# sasa5.net
KiCad netlist of a schematic drawn in EAGLE
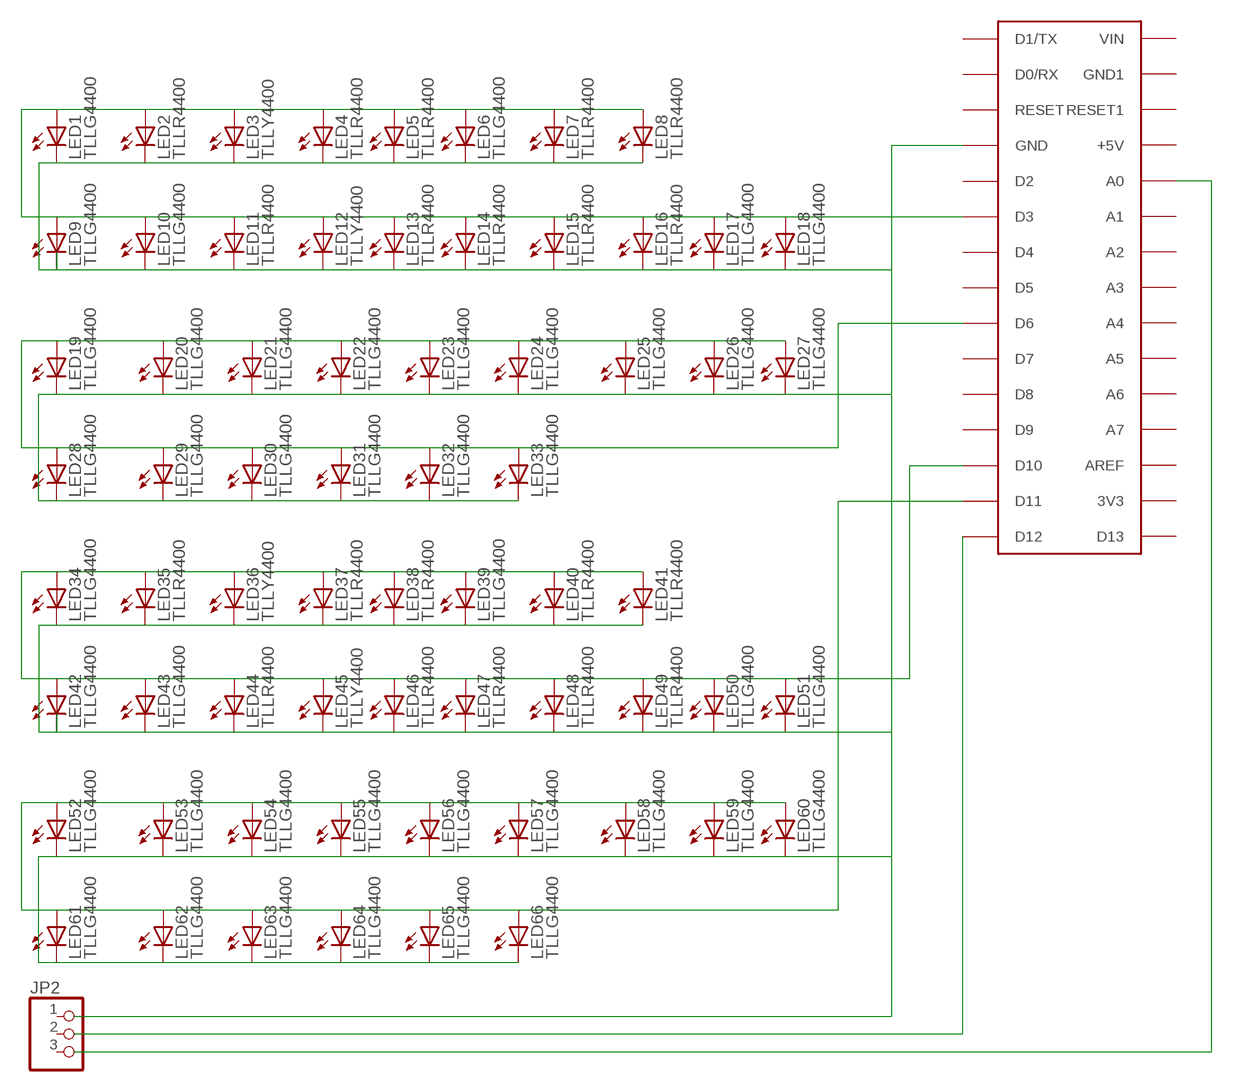
[diagram p0: schematic, sheet 1]

(export (version "E")
  (design (tool "Eeschema 10.0.6"))
  (components
    (comp (ref "JP2")
      (value "PINHD-1X3")
      (footprint "eagle-import:1X03")
      (libsource (lib "eagle-import") (part "PINHD-1X3"))
    )
    (comp (ref "LED1")
      (value "TLLG4400")
      (footprint "eagle-import:LED3MM")
      (fields (field (name "MF") "VISHAY SEMICONDUCTOR"))
      (libsource (lib "eagle-import") (part "TLLG4400"))
    )
    (comp (ref "LED2")
      (value "TLLR4400")
      (footprint "eagle-import:LED3MM")
      (fields (field (name "MF") "VISHAY SEMICONDUCTOR"))
      (libsource (lib "eagle-import") (part "TLLR4400"))
    )
    (comp (ref "LED3")
      (value "TLLY4400")
      (footprint "eagle-import:LED3MM")
      (fields (field (name "MF") "VISHAY SEMICONDUCTOR"))
      (libsource (lib "eagle-import") (part "TLLY4400"))
    )
    (comp (ref "LED4")
      (value "TLLR4400")
      (footprint "eagle-import:LED3MM")
      (fields (field (name "MF") "VISHAY SEMICONDUCTOR"))
      (libsource (lib "eagle-import") (part "TLLR4400"))
    )
    (comp (ref "LED5")
      (value "TLLR4400")
      (footprint "eagle-import:LED3MM")
      (fields (field (name "MF") "VISHAY SEMICONDUCTOR"))
      (libsource (lib "eagle-import") (part "TLLR4400"))
    )
    (comp (ref "LED6")
      (value "TLLG4400")
      (footprint "eagle-import:LED3MM")
      (fields (field (name "MF") "VISHAY SEMICONDUCTOR"))
      (libsource (lib "eagle-import") (part "TLLG4400"))
    )
    (comp (ref "LED7")
      (value "TLLR4400")
      (footprint "eagle-import:LED3MM")
      (fields (field (name "MF") "VISHAY SEMICONDUCTOR"))
      (libsource (lib "eagle-import") (part "TLLR4400"))
    )
    (comp (ref "LED8")
      (value "TLLR4400")
      (footprint "eagle-import:LED3MM")
      (fields (field (name "MF") "VISHAY SEMICONDUCTOR"))
      (libsource (lib "eagle-import") (part "TLLR4400"))
    )
    (comp (ref "LED9")
      (value "TLLG4400")
      (footprint "eagle-import:LED3MM")
      (fields (field (name "MF") "VISHAY SEMICONDUCTOR"))
      (libsource (lib "eagle-import") (part "TLLG4400"))
    )
    (comp (ref "LED10")
      (value "TLLG4400")
      (footprint "eagle-import:LED3MM")
      (fields (field (name "MF") "VISHAY SEMICONDUCTOR"))
      (libsource (lib "eagle-import") (part "TLLG4400"))
    )
    (comp (ref "LED11")
      (value "TLLR4400")
      (footprint "eagle-import:LED3MM")
      (fields (field (name "MF") "VISHAY SEMICONDUCTOR"))
      (libsource (lib "eagle-import") (part "TLLR4400"))
    )
    (comp (ref "LED12")
      (value "TLLY4400")
      (footprint "eagle-import:LED3MM")
      (fields (field (name "MF") "VISHAY SEMICONDUCTOR"))
      (libsource (lib "eagle-import") (part "TLLY4400"))
    )
    (comp (ref "LED13")
      (value "TLLR4400")
      (footprint "eagle-import:LED3MM")
      (fields (field (name "MF") "VISHAY SEMICONDUCTOR"))
      (libsource (lib "eagle-import") (part "TLLR4400"))
    )
    (comp (ref "LED14")
      (value "TLLR4400")
      (footprint "eagle-import:LED3MM")
      (fields (field (name "MF") "VISHAY SEMICONDUCTOR"))
      (libsource (lib "eagle-import") (part "TLLR4400"))
    )
    (comp (ref "LED15")
      (value "TLLR4400")
      (footprint "eagle-import:LED3MM")
      (fields (field (name "MF") "VISHAY SEMICONDUCTOR"))
      (libsource (lib "eagle-import") (part "TLLR4400"))
    )
    (comp (ref "LED16")
      (value "TLLR4400")
      (footprint "eagle-import:LED3MM")
      (fields (field (name "MF") "VISHAY SEMICONDUCTOR"))
      (libsource (lib "eagle-import") (part "TLLR4400"))
    )
    (comp (ref "LED17")
      (value "TLLG4400")
      (footprint "eagle-import:LED3MM")
      (fields (field (name "MF") "VISHAY SEMICONDUCTOR"))
      (libsource (lib "eagle-import") (part "TLLG4400"))
    )
    (comp (ref "LED18")
      (value "TLLG4400")
      (footprint "eagle-import:LED3MM")
      (fields (field (name "MF") "VISHAY SEMICONDUCTOR"))
      (libsource (lib "eagle-import") (part "TLLG4400"))
    )
    (comp (ref "LED19")
      (value "TLLG4400")
      (footprint "eagle-import:LED3MM")
      (fields (field (name "MF") "VISHAY SEMICONDUCTOR"))
      (libsource (lib "eagle-import") (part "TLLG4400"))
    )
    (comp (ref "LED20")
      (value "TLLG4400")
      (footprint "eagle-import:LED3MM")
      (fields (field (name "MF") "VISHAY SEMICONDUCTOR"))
      (libsource (lib "eagle-import") (part "TLLG4400"))
    )
    (comp (ref "LED21")
      (value "TLLG4400")
      (footprint "eagle-import:LED3MM")
      (fields (field (name "MF") "VISHAY SEMICONDUCTOR"))
      (libsource (lib "eagle-import") (part "TLLG4400"))
    )
    (comp (ref "LED22")
      (value "TLLG4400")
      (footprint "eagle-import:LED3MM")
      (fields (field (name "MF") "VISHAY SEMICONDUCTOR"))
      (libsource (lib "eagle-import") (part "TLLG4400"))
    )
    (comp (ref "LED23")
      (value "TLLG4400")
      (footprint "eagle-import:LED3MM")
      (fields (field (name "MF") "VISHAY SEMICONDUCTOR"))
      (libsource (lib "eagle-import") (part "TLLG4400"))
    )
    (comp (ref "LED24")
      (value "TLLG4400")
      (footprint "eagle-import:LED3MM")
      (fields (field (name "MF") "VISHAY SEMICONDUCTOR"))
      (libsource (lib "eagle-import") (part "TLLG4400"))
    )
    (comp (ref "LED25")
      (value "TLLG4400")
      (footprint "eagle-import:LED3MM")
      (fields (field (name "MF") "VISHAY SEMICONDUCTOR"))
      (libsource (lib "eagle-import") (part "TLLG4400"))
    )
    (comp (ref "LED26")
      (value "TLLG4400")
      (footprint "eagle-import:LED3MM")
      (fields (field (name "MF") "VISHAY SEMICONDUCTOR"))
      (libsource (lib "eagle-import") (part "TLLG4400"))
    )
    (comp (ref "LED27")
      (value "TLLG4400")
      (footprint "eagle-import:LED3MM")
      (fields (field (name "MF") "VISHAY SEMICONDUCTOR"))
      (libsource (lib "eagle-import") (part "TLLG4400"))
    )
    (comp (ref "LED28")
      (value "TLLG4400")
      (footprint "eagle-import:LED3MM")
      (fields (field (name "MF") "VISHAY SEMICONDUCTOR"))
      (libsource (lib "eagle-import") (part "TLLG4400"))
    )
    (comp (ref "LED29")
      (value "TLLG4400")
      (footprint "eagle-import:LED3MM")
      (fields (field (name "MF") "VISHAY SEMICONDUCTOR"))
      (libsource (lib "eagle-import") (part "TLLG4400"))
    )
    (comp (ref "LED30")
      (value "TLLG4400")
      (footprint "eagle-import:LED3MM")
      (fields (field (name "MF") "VISHAY SEMICONDUCTOR"))
      (libsource (lib "eagle-import") (part "TLLG4400"))
    )
    (comp (ref "LED31")
      (value "TLLG4400")
      (footprint "eagle-import:LED3MM")
      (fields (field (name "MF") "VISHAY SEMICONDUCTOR"))
      (libsource (lib "eagle-import") (part "TLLG4400"))
    )
    (comp (ref "LED32")
      (value "TLLG4400")
      (footprint "eagle-import:LED3MM")
      (fields (field (name "MF") "VISHAY SEMICONDUCTOR"))
      (libsource (lib "eagle-import") (part "TLLG4400"))
    )
    (comp (ref "LED33")
      (value "TLLG4400")
      (footprint "eagle-import:LED3MM")
      (fields (field (name "MF") "VISHAY SEMICONDUCTOR"))
      (libsource (lib "eagle-import") (part "TLLG4400"))
    )
    (comp (ref "LED34")
      (value "TLLG4400")
      (footprint "eagle-import:LED3MM")
      (fields (field (name "MF") "VISHAY SEMICONDUCTOR"))
      (libsource (lib "eagle-import") (part "TLLG4400"))
    )
    (comp (ref "LED35")
      (value "TLLR4400")
      (footprint "eagle-import:LED3MM")
      (fields (field (name "MF") "VISHAY SEMICONDUCTOR"))
      (libsource (lib "eagle-import") (part "TLLR4400"))
    )
    (comp (ref "LED36")
      (value "TLLY4400")
      (footprint "eagle-import:LED3MM")
      (fields (field (name "MF") "VISHAY SEMICONDUCTOR"))
      (libsource (lib "eagle-import") (part "TLLY4400"))
    )
    (comp (ref "LED37")
      (value "TLLR4400")
      (footprint "eagle-import:LED3MM")
      (fields (field (name "MF") "VISHAY SEMICONDUCTOR"))
      (libsource (lib "eagle-import") (part "TLLR4400"))
    )
    (comp (ref "LED38")
      (value "TLLR4400")
      (footprint "eagle-import:LED3MM")
      (fields (field (name "MF") "VISHAY SEMICONDUCTOR"))
      (libsource (lib "eagle-import") (part "TLLR4400"))
    )
    (comp (ref "LED39")
      (value "TLLG4400")
      (footprint "eagle-import:LED3MM")
      (fields (field (name "MF") "VISHAY SEMICONDUCTOR"))
      (libsource (lib "eagle-import") (part "TLLG4400"))
    )
    (comp (ref "LED40")
      (value "TLLR4400")
      (footprint "eagle-import:LED3MM")
      (fields (field (name "MF") "VISHAY SEMICONDUCTOR"))
      (libsource (lib "eagle-import") (part "TLLR4400"))
    )
    (comp (ref "LED41")
      (value "TLLR4400")
      (footprint "eagle-import:LED3MM")
      (fields (field (name "MF") "VISHAY SEMICONDUCTOR"))
      (libsource (lib "eagle-import") (part "TLLR4400"))
    )
    (comp (ref "LED42")
      (value "TLLG4400")
      (footprint "eagle-import:LED3MM")
      (fields (field (name "MF") "VISHAY SEMICONDUCTOR"))
      (libsource (lib "eagle-import") (part "TLLG4400"))
    )
    (comp (ref "LED43")
      (value "TLLG4400")
      (footprint "eagle-import:LED3MM")
      (fields (field (name "MF") "VISHAY SEMICONDUCTOR"))
      (libsource (lib "eagle-import") (part "TLLG4400"))
    )
    (comp (ref "LED44")
      (value "TLLR4400")
      (footprint "eagle-import:LED3MM")
      (fields (field (name "MF") "VISHAY SEMICONDUCTOR"))
      (libsource (lib "eagle-import") (part "TLLR4400"))
    )
    (comp (ref "LED45")
      (value "TLLY4400")
      (footprint "eagle-import:LED3MM")
      (fields (field (name "MF") "VISHAY SEMICONDUCTOR"))
      (libsource (lib "eagle-import") (part "TLLY4400"))
    )
    (comp (ref "LED46")
      (value "TLLR4400")
      (footprint "eagle-import:LED3MM")
      (fields (field (name "MF") "VISHAY SEMICONDUCTOR"))
      (libsource (lib "eagle-import") (part "TLLR4400"))
    )
    (comp (ref "LED47")
      (value "TLLR4400")
      (footprint "eagle-import:LED3MM")
      (fields (field (name "MF") "VISHAY SEMICONDUCTOR"))
      (libsource (lib "eagle-import") (part "TLLR4400"))
    )
    (comp (ref "LED48")
      (value "TLLR4400")
      (footprint "eagle-import:LED3MM")
      (fields (field (name "MF") "VISHAY SEMICONDUCTOR"))
      (libsource (lib "eagle-import") (part "TLLR4400"))
    )
    (comp (ref "LED49")
      (value "TLLR4400")
      (footprint "eagle-import:LED3MM")
      (fields (field (name "MF") "VISHAY SEMICONDUCTOR"))
      (libsource (lib "eagle-import") (part "TLLR4400"))
    )
    (comp (ref "LED50")
      (value "TLLG4400")
      (footprint "eagle-import:LED3MM")
      (fields (field (name "MF") "VISHAY SEMICONDUCTOR"))
      (libsource (lib "eagle-import") (part "TLLG4400"))
    )
    (comp (ref "LED51")
      (value "TLLG4400")
      (footprint "eagle-import:LED3MM")
      (fields (field (name "MF") "VISHAY SEMICONDUCTOR"))
      (libsource (lib "eagle-import") (part "TLLG4400"))
    )
    (comp (ref "LED52")
      (value "TLLG4400")
      (footprint "eagle-import:LED3MM")
      (fields (field (name "MF") "VISHAY SEMICONDUCTOR"))
      (libsource (lib "eagle-import") (part "TLLG4400"))
    )
    (comp (ref "LED53")
      (value "TLLG4400")
      (footprint "eagle-import:LED3MM")
      (fields (field (name "MF") "VISHAY SEMICONDUCTOR"))
      (libsource (lib "eagle-import") (part "TLLG4400"))
    )
    (comp (ref "LED54")
      (value "TLLG4400")
      (footprint "eagle-import:LED3MM")
      (fields (field (name "MF") "VISHAY SEMICONDUCTOR"))
      (libsource (lib "eagle-import") (part "TLLG4400"))
    )
    (comp (ref "LED55")
      (value "TLLG4400")
      (footprint "eagle-import:LED3MM")
      (fields (field (name "MF") "VISHAY SEMICONDUCTOR"))
      (libsource (lib "eagle-import") (part "TLLG4400"))
    )
    (comp (ref "LED56")
      (value "TLLG4400")
      (footprint "eagle-import:LED3MM")
      (fields (field (name "MF") "VISHAY SEMICONDUCTOR"))
      (libsource (lib "eagle-import") (part "TLLG4400"))
    )
    (comp (ref "LED57")
      (value "TLLG4400")
      (footprint "eagle-import:LED3MM")
      (fields (field (name "MF") "VISHAY SEMICONDUCTOR"))
      (libsource (lib "eagle-import") (part "TLLG4400"))
    )
    (comp (ref "LED58")
      (value "TLLG4400")
      (footprint "eagle-import:LED3MM")
      (fields (field (name "MF") "VISHAY SEMICONDUCTOR"))
      (libsource (lib "eagle-import") (part "TLLG4400"))
    )
    (comp (ref "LED59")
      (value "TLLG4400")
      (footprint "eagle-import:LED3MM")
      (fields (field (name "MF") "VISHAY SEMICONDUCTOR"))
      (libsource (lib "eagle-import") (part "TLLG4400"))
    )
    (comp (ref "LED60")
      (value "TLLG4400")
      (footprint "eagle-import:LED3MM")
      (fields (field (name "MF") "VISHAY SEMICONDUCTOR"))
      (libsource (lib "eagle-import") (part "TLLG4400"))
    )
    (comp (ref "LED61")
      (value "TLLG4400")
      (footprint "eagle-import:LED3MM")
      (fields (field (name "MF") "VISHAY SEMICONDUCTOR"))
      (libsource (lib "eagle-import") (part "TLLG4400"))
    )
    (comp (ref "LED62")
      (value "TLLG4400")
      (footprint "eagle-import:LED3MM")
      (fields (field (name "MF") "VISHAY SEMICONDUCTOR"))
      (libsource (lib "eagle-import") (part "TLLG4400"))
    )
    (comp (ref "LED63")
      (value "TLLG4400")
      (footprint "eagle-import:LED3MM")
      (fields (field (name "MF") "VISHAY SEMICONDUCTOR"))
      (libsource (lib "eagle-import") (part "TLLG4400"))
    )
    (comp (ref "LED64")
      (value "TLLG4400")
      (footprint "eagle-import:LED3MM")
      (fields (field (name "MF") "VISHAY SEMICONDUCTOR"))
      (libsource (lib "eagle-import") (part "TLLG4400"))
    )
    (comp (ref "LED65")
      (value "TLLG4400")
      (footprint "eagle-import:LED3MM")
      (fields (field (name "MF") "VISHAY SEMICONDUCTOR"))
      (libsource (lib "eagle-import") (part "TLLG4400"))
    )
    (comp (ref "LED66")
      (value "TLLG4400")
      (footprint "eagle-import:LED3MM")
      (fields (field (name "MF") "VISHAY SEMICONDUCTOR"))
      (libsource (lib "eagle-import") (part "TLLG4400"))
    )
    (comp (ref "U$4")
      (value "ARDUINONANO")
      (footprint "eagle-import:PDIP-32")
      (libsource (lib "eagle-import") (part "ARDUINONANO"))
    )
  )
  (nets
    (net (code "1") (name "Net-(LED1-C)") (class "Default")
      (node (ref "LED1") (pin "K") (pinfunction "C_K") (pintype "passive"))
      (node (ref "LED10") (pin "K") (pinfunction "C_K") (pintype "passive"))
      (node (ref "LED11") (pin "K") (pinfunction "C_K") (pintype "passive"))
      (node (ref "LED12") (pin "K") (pinfunction "C_K") (pintype "passive"))
      (node (ref "LED13") (pin "K") (pinfunction "C_K") (pintype "passive"))
      (node (ref "LED14") (pin "K") (pinfunction "C_K") (pintype "passive"))
      (node (ref "LED15") (pin "K") (pinfunction "C_K") (pintype "passive"))
      (node (ref "LED16") (pin "K") (pinfunction "C_K") (pintype "passive"))
      (node (ref "LED17") (pin "K") (pinfunction "C_K") (pintype "passive"))
      (node (ref "LED18") (pin "K") (pinfunction "C_K") (pintype "passive"))
      (node (ref "LED19") (pin "K") (pinfunction "C_K") (pintype "passive"))
      (node (ref "LED2") (pin "K") (pinfunction "C_K") (pintype "passive"))
      (node (ref "LED20") (pin "K") (pinfunction "C_K") (pintype "passive"))
      (node (ref "LED21") (pin "K") (pinfunction "C_K") (pintype "passive"))
      (node (ref "LED22") (pin "K") (pinfunction "C_K") (pintype "passive"))
      (node (ref "LED23") (pin "K") (pinfunction "C_K") (pintype "passive"))
      (node (ref "LED24") (pin "K") (pinfunction "C_K") (pintype "passive"))
      (node (ref "LED25") (pin "K") (pinfunction "C_K") (pintype "passive"))
      (node (ref "LED26") (pin "K") (pinfunction "C_K") (pintype "passive"))
      (node (ref "LED27") (pin "K") (pinfunction "C_K") (pintype "passive"))
      (node (ref "LED28") (pin "K") (pinfunction "C_K") (pintype "passive"))
      (node (ref "LED29") (pin "K") (pinfunction "C_K") (pintype "passive"))
      (node (ref "LED3") (pin "K") (pinfunction "C_K") (pintype "passive"))
      (node (ref "LED30") (pin "K") (pinfunction "C_K") (pintype "passive"))
      (node (ref "LED31") (pin "K") (pinfunction "C_K") (pintype "passive"))
      (node (ref "LED32") (pin "K") (pinfunction "C_K") (pintype "passive"))
      (node (ref "LED33") (pin "K") (pinfunction "C_K") (pintype "passive"))
      (node (ref "LED34") (pin "K") (pinfunction "C_K") (pintype "passive"))
      (node (ref "LED35") (pin "K") (pinfunction "C_K") (pintype "passive"))
      (node (ref "LED36") (pin "K") (pinfunction "C_K") (pintype "passive"))
      (node (ref "LED37") (pin "K") (pinfunction "C_K") (pintype "passive"))
      (node (ref "LED38") (pin "K") (pinfunction "C_K") (pintype "passive"))
      (node (ref "LED39") (pin "K") (pinfunction "C_K") (pintype "passive"))
      (node (ref "LED4") (pin "K") (pinfunction "C_K") (pintype "passive"))
      (node (ref "LED40") (pin "K") (pinfunction "C_K") (pintype "passive"))
      (node (ref "LED41") (pin "K") (pinfunction "C_K") (pintype "passive"))
      (node (ref "LED42") (pin "K") (pinfunction "C_K") (pintype "passive"))
      (node (ref "LED43") (pin "K") (pinfunction "C_K") (pintype "passive"))
      (node (ref "LED44") (pin "K") (pinfunction "C_K") (pintype "passive"))
      (node (ref "LED45") (pin "K") (pinfunction "C_K") (pintype "passive"))
      (node (ref "LED46") (pin "K") (pinfunction "C_K") (pintype "passive"))
      (node (ref "LED47") (pin "K") (pinfunction "C_K") (pintype "passive"))
      (node (ref "LED48") (pin "K") (pinfunction "C_K") (pintype "passive"))
      (node (ref "LED49") (pin "K") (pinfunction "C_K") (pintype "passive"))
      (node (ref "LED5") (pin "K") (pinfunction "C_K") (pintype "passive"))
      (node (ref "LED50") (pin "K") (pinfunction "C_K") (pintype "passive"))
      (node (ref "LED51") (pin "K") (pinfunction "C_K") (pintype "passive"))
      (node (ref "LED52") (pin "K") (pinfunction "C_K") (pintype "passive"))
      (node (ref "LED53") (pin "K") (pinfunction "C_K") (pintype "passive"))
      (node (ref "LED54") (pin "K") (pinfunction "C_K") (pintype "passive"))
      (node (ref "LED55") (pin "K") (pinfunction "C_K") (pintype "passive"))
      (node (ref "LED56") (pin "K") (pinfunction "C_K") (pintype "passive"))
      (node (ref "LED57") (pin "K") (pinfunction "C_K") (pintype "passive"))
      (node (ref "LED58") (pin "K") (pinfunction "C_K") (pintype "passive"))
      (node (ref "LED59") (pin "K") (pinfunction "C_K") (pintype "passive"))
      (node (ref "LED6") (pin "K") (pinfunction "C_K") (pintype "passive"))
      (node (ref "LED60") (pin "K") (pinfunction "C_K") (pintype "passive"))
      (node (ref "LED61") (pin "K") (pinfunction "C_K") (pintype "passive"))
      (node (ref "LED62") (pin "K") (pinfunction "C_K") (pintype "passive"))
      (node (ref "LED63") (pin "K") (pinfunction "C_K") (pintype "passive"))
      (node (ref "LED64") (pin "K") (pinfunction "C_K") (pintype "passive"))
      (node (ref "LED65") (pin "K") (pinfunction "C_K") (pintype "passive"))
      (node (ref "LED66") (pin "K") (pinfunction "C_K") (pintype "passive"))
      (node (ref "LED7") (pin "K") (pinfunction "C_K") (pintype "passive"))
      (node (ref "LED8") (pin "K") (pinfunction "C_K") (pintype "passive"))
      (node (ref "LED9") (pin "K") (pinfunction "C_K") (pintype "passive"))
      (node (ref "U$4") (pin "GND") (pinfunction "GND_GND") (pintype "bidirectional"))
    )
    (net (code "2") (name "Net-(LED1-PadA)") (class "Default")
      (node (ref "LED1") (pin "A") (pinfunction "A_A") (pintype "passive"))
      (node (ref "LED10") (pin "A") (pinfunction "A_A") (pintype "passive"))
      (node (ref "LED11") (pin "A") (pinfunction "A_A") (pintype "passive"))
      (node (ref "LED12") (pin "A") (pinfunction "A_A") (pintype "passive"))
      (node (ref "LED13") (pin "A") (pinfunction "A_A") (pintype "passive"))
      (node (ref "LED14") (pin "A") (pinfunction "A_A") (pintype "passive"))
      (node (ref "LED15") (pin "A") (pinfunction "A_A") (pintype "passive"))
      (node (ref "LED16") (pin "A") (pinfunction "A_A") (pintype "passive"))
      (node (ref "LED17") (pin "A") (pinfunction "A_A") (pintype "passive"))
      (node (ref "LED18") (pin "A") (pinfunction "A_A") (pintype "passive"))
      (node (ref "LED2") (pin "A") (pinfunction "A_A") (pintype "passive"))
      (node (ref "LED3") (pin "A") (pinfunction "A_A") (pintype "passive"))
      (node (ref "LED4") (pin "A") (pinfunction "A_A") (pintype "passive"))
      (node (ref "LED5") (pin "A") (pinfunction "A_A") (pintype "passive"))
      (node (ref "LED6") (pin "A") (pinfunction "A_A") (pintype "passive"))
      (node (ref "LED7") (pin "A") (pinfunction "A_A") (pintype "passive"))
      (node (ref "LED8") (pin "A") (pinfunction "A_A") (pintype "passive"))
      (node (ref "LED9") (pin "A") (pinfunction "A_A") (pintype "passive"))
      (node (ref "U$4") (pin "D3") (pinfunction "D3_D3") (pintype "bidirectional"))
    )
    (net (code "3") (name "Net-(LED19-PadA)") (class "Default")
      (node (ref "LED19") (pin "A") (pinfunction "A_A") (pintype "passive"))
      (node (ref "LED20") (pin "A") (pinfunction "A_A") (pintype "passive"))
      (node (ref "LED21") (pin "A") (pinfunction "A_A") (pintype "passive"))
      (node (ref "LED22") (pin "A") (pinfunction "A_A") (pintype "passive"))
      (node (ref "LED23") (pin "A") (pinfunction "A_A") (pintype "passive"))
      (node (ref "LED24") (pin "A") (pinfunction "A_A") (pintype "passive"))
      (node (ref "LED25") (pin "A") (pinfunction "A_A") (pintype "passive"))
      (node (ref "LED26") (pin "A") (pinfunction "A_A") (pintype "passive"))
      (node (ref "LED27") (pin "A") (pinfunction "A_A") (pintype "passive"))
      (node (ref "LED28") (pin "A") (pinfunction "A_A") (pintype "passive"))
      (node (ref "LED29") (pin "A") (pinfunction "A_A") (pintype "passive"))
      (node (ref "LED30") (pin "A") (pinfunction "A_A") (pintype "passive"))
      (node (ref "LED31") (pin "A") (pinfunction "A_A") (pintype "passive"))
      (node (ref "LED32") (pin "A") (pinfunction "A_A") (pintype "passive"))
      (node (ref "LED33") (pin "A") (pinfunction "A_A") (pintype "passive"))
      (node (ref "U$4") (pin "D6") (pinfunction "D6_D6") (pintype "bidirectional"))
    )
    (net (code "4") (name "Net-(LED34-PadA)") (class "Default")
      (node (ref "LED34") (pin "A") (pinfunction "A_A") (pintype "passive"))
      (node (ref "LED35") (pin "A") (pinfunction "A_A") (pintype "passive"))
      (node (ref "LED36") (pin "A") (pinfunction "A_A") (pintype "passive"))
      (node (ref "LED37") (pin "A") (pinfunction "A_A") (pintype "passive"))
      (node (ref "LED38") (pin "A") (pinfunction "A_A") (pintype "passive"))
      (node (ref "LED39") (pin "A") (pinfunction "A_A") (pintype "passive"))
      (node (ref "LED40") (pin "A") (pinfunction "A_A") (pintype "passive"))
      (node (ref "LED41") (pin "A") (pinfunction "A_A") (pintype "passive"))
      (node (ref "LED42") (pin "A") (pinfunction "A_A") (pintype "passive"))
      (node (ref "LED43") (pin "A") (pinfunction "A_A") (pintype "passive"))
      (node (ref "LED44") (pin "A") (pinfunction "A_A") (pintype "passive"))
      (node (ref "LED45") (pin "A") (pinfunction "A_A") (pintype "passive"))
      (node (ref "LED46") (pin "A") (pinfunction "A_A") (pintype "passive"))
      (node (ref "LED47") (pin "A") (pinfunction "A_A") (pintype "passive"))
      (node (ref "LED48") (pin "A") (pinfunction "A_A") (pintype "passive"))
      (node (ref "LED49") (pin "A") (pinfunction "A_A") (pintype "passive"))
      (node (ref "LED50") (pin "A") (pinfunction "A_A") (pintype "passive"))
      (node (ref "LED51") (pin "A") (pinfunction "A_A") (pintype "passive"))
      (node (ref "U$4") (pin "D10") (pinfunction "D10_D10") (pintype "bidirectional"))
    )
    (net (code "5") (name "Net-(LED52-PadA)") (class "Default")
      (node (ref "LED52") (pin "A") (pinfunction "A_A") (pintype "passive"))
      (node (ref "LED53") (pin "A") (pinfunction "A_A") (pintype "passive"))
      (node (ref "LED54") (pin "A") (pinfunction "A_A") (pintype "passive"))
      (node (ref "LED55") (pin "A") (pinfunction "A_A") (pintype "passive"))
      (node (ref "LED56") (pin "A") (pinfunction "A_A") (pintype "passive"))
      (node (ref "LED57") (pin "A") (pinfunction "A_A") (pintype "passive"))
      (node (ref "LED58") (pin "A") (pinfunction "A_A") (pintype "passive"))
      (node (ref "LED59") (pin "A") (pinfunction "A_A") (pintype "passive"))
      (node (ref "LED60") (pin "A") (pinfunction "A_A") (pintype "passive"))
      (node (ref "LED61") (pin "A") (pinfunction "A_A") (pintype "passive"))
      (node (ref "LED62") (pin "A") (pinfunction "A_A") (pintype "passive"))
      (node (ref "LED63") (pin "A") (pinfunction "A_A") (pintype "passive"))
      (node (ref "LED64") (pin "A") (pinfunction "A_A") (pintype "passive"))
      (node (ref "LED65") (pin "A") (pinfunction "A_A") (pintype "passive"))
      (node (ref "LED66") (pin "A") (pinfunction "A_A") (pintype "passive"))
      (node (ref "U$4") (pin "D11") (pinfunction "D11_D11") (pintype "bidirectional"))
    )
    (net (code "6") (name "unconnected-(JP2-Pad1)") (class "Default")
      (node (ref "JP2") (pin "1") (pinfunction "1_1") (pintype "passive"))
    )
    (net (code "7") (name "unconnected-(JP2-Pad2)") (class "Default")
      (node (ref "JP2") (pin "2") (pinfunction "2_2") (pintype "passive"))
    )
    (net (code "8") (name "unconnected-(JP2-Pad3)") (class "Default")
      (node (ref "JP2") (pin "3") (pinfunction "3_3") (pintype "passive"))
    )
    (net (code "9") (name "unconnected-(U$4-Pad+5V)") (class "Default")
      (node (ref "U$4") (pin "+5V") (pinfunction "+5V_+5V") (pintype "bidirectional"))
    )
    (net (code "10") (name "unconnected-(U$4-Pad3V3)") (class "Default")
      (node (ref "U$4") (pin "3V3") (pinfunction "3V3_3V3") (pintype "bidirectional"))
    )
    (net (code "11") (name "unconnected-(U$4-PadA0)") (class "Default")
      (node (ref "U$4") (pin "A0") (pinfunction "A0_A0") (pintype "bidirectional"))
    )
    (net (code "12") (name "unconnected-(U$4-PadA1)") (class "Default")
      (node (ref "U$4") (pin "A1") (pinfunction "A1_A1") (pintype "bidirectional"))
    )
    (net (code "13") (name "unconnected-(U$4-PadA2)") (class "Default")
      (node (ref "U$4") (pin "A2") (pinfunction "A2_A2") (pintype "bidirectional"))
    )
    (net (code "14") (name "unconnected-(U$4-PadA3)") (class "Default")
      (node (ref "U$4") (pin "A3") (pinfunction "A3_A3") (pintype "bidirectional"))
    )
    (net (code "15") (name "unconnected-(U$4-PadA4)") (class "Default")
      (node (ref "U$4") (pin "A4") (pinfunction "A4_A4") (pintype "bidirectional"))
    )
    (net (code "16") (name "unconnected-(U$4-PadA5)") (class "Default")
      (node (ref "U$4") (pin "A5") (pinfunction "A5_A5") (pintype "bidirectional"))
    )
    (net (code "17") (name "unconnected-(U$4-PadA6)") (class "Default")
      (node (ref "U$4") (pin "A6") (pinfunction "A6_A6") (pintype "bidirectional"))
    )
    (net (code "18") (name "unconnected-(U$4-PadA7)") (class "Default")
      (node (ref "U$4") (pin "A7") (pinfunction "A7_A7") (pintype "bidirectional"))
    )
    (net (code "19") (name "unconnected-(U$4-PadAREF)") (class "Default")
      (node (ref "U$4") (pin "AREF") (pinfunction "AREF_AREF") (pintype "bidirectional"))
    )
    (net (code "20") (name "unconnected-(U$4-PadD0{slash}RX)") (class "Default")
      (node (ref "U$4") (pin "D0/RX") (pinfunction "D0/RX_D0/RX") (pintype "bidirectional"))
    )
    (net (code "21") (name "unconnected-(U$4-PadD1{slash}TX)") (class "Default")
      (node (ref "U$4") (pin "D1/TX") (pinfunction "D1/TX_D1/TX") (pintype "bidirectional"))
    )
    (net (code "22") (name "unconnected-(U$4-PadD2)") (class "Default")
      (node (ref "U$4") (pin "D2") (pinfunction "D2_D2") (pintype "bidirectional"))
    )
    (net (code "23") (name "unconnected-(U$4-PadD4)") (class "Default")
      (node (ref "U$4") (pin "D4") (pinfunction "D4_D4") (pintype "bidirectional"))
    )
    (net (code "24") (name "unconnected-(U$4-PadD5)") (class "Default")
      (node (ref "U$4") (pin "D5") (pinfunction "D5_D5") (pintype "bidirectional"))
    )
    (net (code "25") (name "unconnected-(U$4-PadD7)") (class "Default")
      (node (ref "U$4") (pin "D7") (pinfunction "D7_D7") (pintype "bidirectional"))
    )
    (net (code "26") (name "unconnected-(U$4-PadD8)") (class "Default")
      (node (ref "U$4") (pin "D8") (pinfunction "D8_D8") (pintype "bidirectional"))
    )
    (net (code "27") (name "unconnected-(U$4-PadD9)") (class "Default")
      (node (ref "U$4") (pin "D9") (pinfunction "D9_D9") (pintype "bidirectional"))
    )
    (net (code "28") (name "unconnected-(U$4-PadD12)") (class "Default")
      (node (ref "U$4") (pin "D12") (pinfunction "D12_D12") (pintype "bidirectional"))
    )
    (net (code "29") (name "unconnected-(U$4-PadD13)") (class "Default")
      (node (ref "U$4") (pin "D13") (pinfunction "D13_D13") (pintype "bidirectional"))
    )
    (net (code "30") (name "unconnected-(U$4-PadGND1)") (class "Default")
      (node (ref "U$4") (pin "GND1") (pinfunction "GND1_GND1") (pintype "bidirectional"))
    )
    (net (code "31") (name "unconnected-(U$4-PadRESET)") (class "Default")
      (node (ref "U$4") (pin "RESET") (pinfunction "RESET_RESET") (pintype "bidirectional"))
    )
    (net (code "32") (name "unconnected-(U$4-PadRESET1)") (class "Default")
      (node (ref "U$4") (pin "RESET1") (pinfunction "RESET1_RESET1") (pintype "bidirectional"))
    )
    (net (code "33") (name "unconnected-(U$4-PadVIN)") (class "Default")
      (node (ref "U$4") (pin "VIN") (pinfunction "VIN_VIN") (pintype "bidirectional"))
    )
  )
)
